# RegisterA.net
KiCad netlist of a schematic drawn in Altium Designer
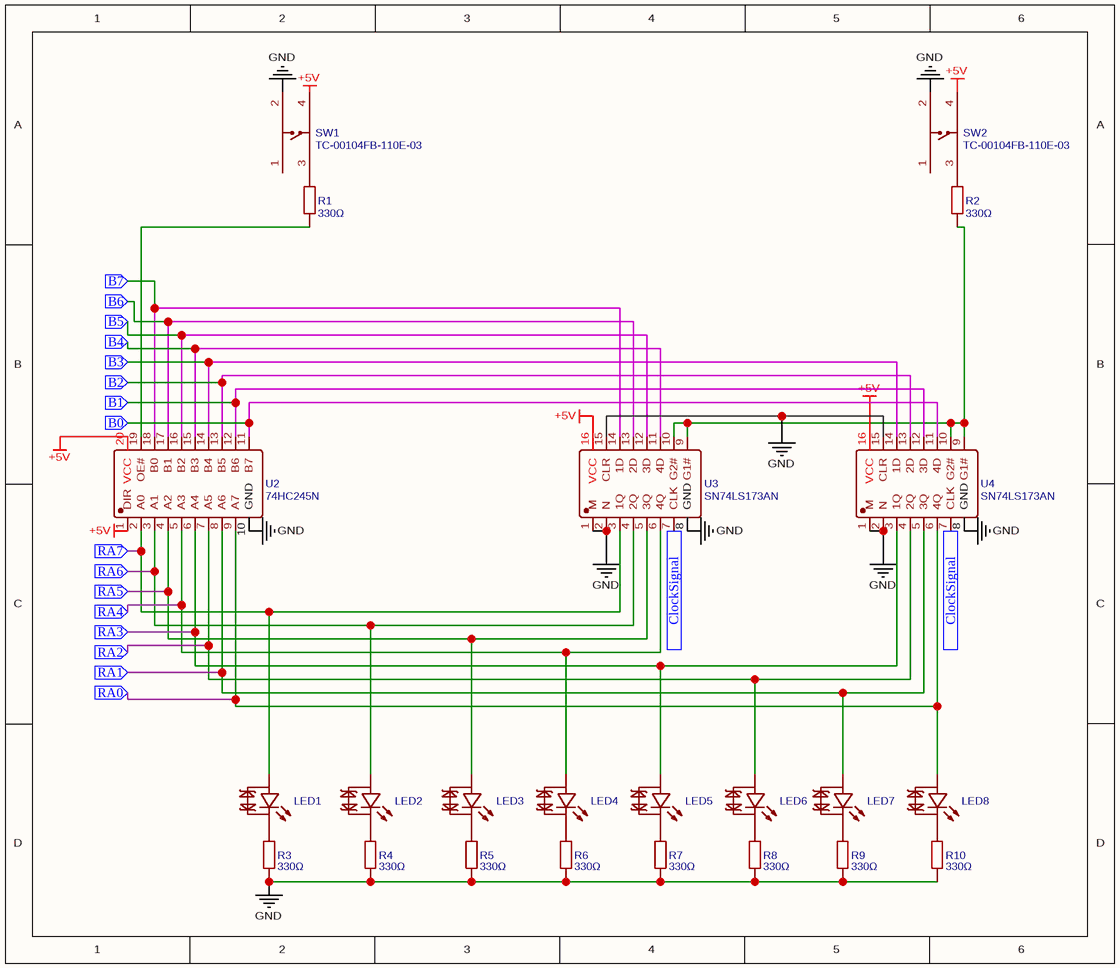
[diagram p0: RegisterA.schdoc]

(export (version "E")
  (design (tool "Eeschema 10.0.6"))
  (components
    (comp (ref "LED1")
      (value "204-15UTC/S400-X9-L")
      (fields (field (name "MANUFACTURER") "EVERLIGHT(亿光)") (field (name "CONTRIBUTOR") "LCSC"))
      (libsource (lib "altium-import") (part "root_3_204-15UTC/S400-X9-L_"))
    )
    (comp (ref "LED2")
      (value "204-15UTC/S400-X9-L")
      (fields (field (name "MANUFACTURER") "EVERLIGHT(亿光)") (field (name "CONTRIBUTOR") "LCSC"))
      (libsource (lib "altium-import") (part "root_3_204-15UTC/S400-X9-L_"))
    )
    (comp (ref "LED3")
      (value "204-15UTC/S400-X9-L")
      (fields (field (name "MANUFACTURER") "EVERLIGHT(亿光)") (field (name "CONTRIBUTOR") "LCSC"))
      (libsource (lib "altium-import") (part "root_3_204-15UTC/S400-X9-L_"))
    )
    (comp (ref "LED4")
      (value "204-15UTC/S400-X9-L")
      (fields (field (name "MANUFACTURER") "EVERLIGHT(亿光)") (field (name "CONTRIBUTOR") "LCSC"))
      (libsource (lib "altium-import") (part "root_3_204-15UTC/S400-X9-L_"))
    )
    (comp (ref "LED5")
      (value "204-15UTC/S400-X9-L")
      (fields (field (name "MANUFACTURER") "EVERLIGHT(亿光)") (field (name "CONTRIBUTOR") "LCSC"))
      (libsource (lib "altium-import") (part "root_3_204-15UTC/S400-X9-L_"))
    )
    (comp (ref "LED6")
      (value "204-15UTC/S400-X9-L")
      (fields (field (name "MANUFACTURER") "EVERLIGHT(亿光)") (field (name "CONTRIBUTOR") "LCSC"))
      (libsource (lib "altium-import") (part "root_3_204-15UTC/S400-X9-L_"))
    )
    (comp (ref "LED7")
      (value "204-15UTC/S400-X9-L")
      (fields (field (name "MANUFACTURER") "EVERLIGHT(亿光)") (field (name "CONTRIBUTOR") "LCSC"))
      (libsource (lib "altium-import") (part "root_3_204-15UTC/S400-X9-L_"))
    )
    (comp (ref "LED8")
      (value "204-15UTC/S400-X9-L")
      (fields (field (name "MANUFACTURER") "EVERLIGHT(亿光)") (field (name "CONTRIBUTOR") "LCSC"))
      (libsource (lib "altium-import") (part "root_3_204-15UTC/S400-X9-L_"))
    )
    (comp (ref "R1")
      (value "330Ω")
      (fields
        (field (name "MANUFACTURER") "CCO(千志电子)")
        (field (name "MANUFACTURER PART") "MF1/2W-0.1Ω±1% T")
        (field (name "CONTRIBUTOR") "LCSC")
      )
      (libsource (lib "altium-import") (part "root_1_330Ω_"))
    )
    (comp (ref "R2")
      (value "330Ω")
      (fields
        (field (name "MANUFACTURER") "CCO(千志电子)")
        (field (name "MANUFACTURER PART") "MF1/2W-0.1Ω±1% T")
        (field (name "CONTRIBUTOR") "LCSC")
      )
      (libsource (lib "altium-import") (part "root_1_330Ω_"))
    )
    (comp (ref "R3")
      (value "330Ω")
      (fields
        (field (name "MANUFACTURER") "CCO(千志电子)")
        (field (name "MANUFACTURER PART") "MF1/2W-0.1Ω±1% T")
        (field (name "CONTRIBUTOR") "LCSC")
      )
      (libsource (lib "altium-import") (part "root_3_330Ω_"))
    )
    (comp (ref "R4")
      (value "330Ω")
      (fields
        (field (name "MANUFACTURER") "CCO(千志电子)")
        (field (name "MANUFACTURER PART") "MF1/2W-0.1Ω±1% T")
        (field (name "CONTRIBUTOR") "LCSC")
      )
      (libsource (lib "altium-import") (part "root_3_330Ω_"))
    )
    (comp (ref "R5")
      (value "330Ω")
      (fields
        (field (name "MANUFACTURER") "CCO(千志电子)")
        (field (name "MANUFACTURER PART") "MF1/2W-0.1Ω±1% T")
        (field (name "CONTRIBUTOR") "LCSC")
      )
      (libsource (lib "altium-import") (part "root_3_330Ω_"))
    )
    (comp (ref "R6")
      (value "330Ω")
      (fields
        (field (name "MANUFACTURER") "CCO(千志电子)")
        (field (name "MANUFACTURER PART") "MF1/2W-0.1Ω±1% T")
        (field (name "CONTRIBUTOR") "LCSC")
      )
      (libsource (lib "altium-import") (part "root_3_330Ω_"))
    )
    (comp (ref "R7")
      (value "330Ω")
      (fields
        (field (name "MANUFACTURER") "CCO(千志电子)")
        (field (name "MANUFACTURER PART") "MF1/2W-0.1Ω±1% T")
        (field (name "CONTRIBUTOR") "LCSC")
      )
      (libsource (lib "altium-import") (part "root_3_330Ω_"))
    )
    (comp (ref "R8")
      (value "330Ω")
      (fields
        (field (name "MANUFACTURER") "CCO(千志电子)")
        (field (name "MANUFACTURER PART") "MF1/2W-0.1Ω±1% T")
        (field (name "CONTRIBUTOR") "LCSC")
      )
      (libsource (lib "altium-import") (part "root_3_330Ω_"))
    )
    (comp (ref "R9")
      (value "330Ω")
      (fields
        (field (name "MANUFACTURER") "CCO(千志电子)")
        (field (name "MANUFACTURER PART") "MF1/2W-0.1Ω±1% T")
        (field (name "CONTRIBUTOR") "LCSC")
      )
      (libsource (lib "altium-import") (part "root_3_330Ω_"))
    )
    (comp (ref "R10")
      (value "330Ω")
      (fields
        (field (name "MANUFACTURER") "CCO(千志电子)")
        (field (name "MANUFACTURER PART") "MF1/2W-0.1Ω±1% T")
        (field (name "CONTRIBUTOR") "LCSC")
      )
      (libsource (lib "altium-import") (part "root_3_330Ω_"))
    )
    (comp (ref "SW1")
      (value "TC-00104FB-110E-03")
      (fields (field (name "MANUFACTURER") "HOOYA(皓宇电子)") (field (name "CONTRIBUTOR") "lcsc"))
      (libsource (lib "altium-import") (part "root_1_TC-00104FB-110E-03_"))
    )
    (comp (ref "SW2")
      (value "TC-00104FB-110E-03")
      (fields (field (name "MANUFACTURER") "HOOYA(皓宇电子)") (field (name "CONTRIBUTOR") "lcsc"))
      (libsource (lib "altium-import") (part "root_1_TC-00104FB-110E-03_"))
    )
    (comp (ref "U2")
      (value "74HC245N")
      (fields (field (name "MANUFACTURER") "HGSEMI(华冠)") (field (name "CONTRIBUTOR") "LCSC"))
      (libsource (lib "altium-import") (part "root_1_74HC245N_"))
    )
    (comp (ref "U3")
      (value "SN74LS173AN")
      (fields (field (name "MANUFACTURER") "TI(德州仪器)") (field (name "CONTRIBUTOR") "LCSC"))
      (libsource (lib "altium-import") (part "root_1_SN74LS173AN_"))
    )
    (comp (ref "U4")
      (value "SN74LS173AN")
      (fields (field (name "MANUFACTURER") "TI(德州仪器)") (field (name "CONTRIBUTOR") "LCSC"))
      (libsource (lib "altium-import") (part "root_1_SN74LS173AN_"))
    )
  )
  (nets
    (net (code "1") (name "+5V") (class "Default")
      (node (ref "SW2") (pin "4") (pinfunction "4_4") (pintype "passive"))
      (node (ref "U2") (pin "1") (pinfunction "DIR_1") (pintype "passive"))
      (node (ref "U2") (pin "20") (pinfunction "VCC_20") (pintype "passive"))
      (node (ref "U3") (pin "16") (pinfunction "VCC_16") (pintype "passive"))
      (node (ref "U4") (pin "16") (pinfunction "VCC_16") (pintype "passive"))
    )
    (net (code "2") (name "/B0") (class "Default")
      (node (ref "U2") (pin "11") (pinfunction "B7_11") (pintype "passive"))
      (node (ref "U4") (pin "11") (pinfunction "4D_11") (pintype "passive"))
    )
    (net (code "3") (name "/B1") (class "Default")
      (node (ref "U2") (pin "12") (pinfunction "B6_12") (pintype "passive"))
      (node (ref "U4") (pin "12") (pinfunction "3D_12") (pintype "passive"))
    )
    (net (code "4") (name "/B2") (class "Default")
      (node (ref "U2") (pin "13") (pinfunction "B5_13") (pintype "passive"))
      (node (ref "U4") (pin "13") (pinfunction "2D_13") (pintype "passive"))
    )
    (net (code "5") (name "/B3") (class "Default")
      (node (ref "U2") (pin "14") (pinfunction "B4_14") (pintype "passive"))
      (node (ref "U4") (pin "14") (pinfunction "1D_14") (pintype "passive"))
    )
    (net (code "6") (name "/B4") (class "Default")
      (node (ref "U2") (pin "15") (pinfunction "B3_15") (pintype "passive"))
      (node (ref "U3") (pin "11") (pinfunction "4D_11") (pintype "passive"))
    )
    (net (code "7") (name "/B5") (class "Default")
      (node (ref "U2") (pin "16") (pinfunction "B2_16") (pintype "passive"))
      (node (ref "U3") (pin "12") (pinfunction "3D_12") (pintype "passive"))
    )
    (net (code "8") (name "/B6") (class "Default")
      (node (ref "U2") (pin "17") (pinfunction "B1_17") (pintype "passive"))
      (node (ref "U3") (pin "13") (pinfunction "2D_13") (pintype "passive"))
    )
    (net (code "9") (name "/B7") (class "Default")
      (node (ref "U2") (pin "18") (pinfunction "B0_18") (pintype "passive"))
      (node (ref "U3") (pin "14") (pinfunction "1D_14") (pintype "passive"))
    )
    (net (code "10") (name "/ClockSignal") (class "Default")
      (node (ref "U3") (pin "7") (pinfunction "CLK_7") (pintype "passive"))
      (node (ref "U4") (pin "7") (pinfunction "CLK_7") (pintype "passive"))
    )
    (net (code "11") (name "/RA0") (class "Default")
      (node (ref "LED8") (pin "1") (pinfunction "A_1") (pintype "passive"))
      (node (ref "U2") (pin "9") (pinfunction "A7_9") (pintype "passive"))
      (node (ref "U4") (pin "6") (pinfunction "4Q_6") (pintype "passive"))
    )
    (net (code "12") (name "/RA1") (class "Default")
      (node (ref "LED7") (pin "1") (pinfunction "A_1") (pintype "passive"))
      (node (ref "U2") (pin "8") (pinfunction "A6_8") (pintype "passive"))
      (node (ref "U4") (pin "5") (pinfunction "3Q_5") (pintype "passive"))
    )
    (net (code "13") (name "/RA2") (class "Default")
      (node (ref "LED6") (pin "1") (pinfunction "A_1") (pintype "passive"))
      (node (ref "U2") (pin "7") (pinfunction "A5_7") (pintype "passive"))
      (node (ref "U4") (pin "4") (pinfunction "2Q_4") (pintype "passive"))
    )
    (net (code "14") (name "/RA3") (class "Default")
      (node (ref "LED5") (pin "1") (pinfunction "A_1") (pintype "passive"))
      (node (ref "U2") (pin "6") (pinfunction "A4_6") (pintype "passive"))
      (node (ref "U4") (pin "3") (pinfunction "1Q_3") (pintype "passive"))
    )
    (net (code "15") (name "/RA4") (class "Default")
      (node (ref "LED4") (pin "1") (pinfunction "A_1") (pintype "passive"))
      (node (ref "U2") (pin "5") (pinfunction "A3_5") (pintype "passive"))
      (node (ref "U3") (pin "6") (pinfunction "4Q_6") (pintype "passive"))
    )
    (net (code "16") (name "/RA5") (class "Default")
      (node (ref "LED3") (pin "1") (pinfunction "A_1") (pintype "passive"))
      (node (ref "U2") (pin "4") (pinfunction "A2_4") (pintype "passive"))
      (node (ref "U3") (pin "5") (pinfunction "3Q_5") (pintype "passive"))
    )
    (net (code "17") (name "/RA6") (class "Default")
      (node (ref "LED2") (pin "1") (pinfunction "A_1") (pintype "passive"))
      (node (ref "U2") (pin "3") (pinfunction "A1_3") (pintype "passive"))
      (node (ref "U3") (pin "4") (pinfunction "2Q_4") (pintype "passive"))
    )
    (net (code "18") (name "/RA7") (class "Default")
      (node (ref "LED1") (pin "1") (pinfunction "A_1") (pintype "passive"))
      (node (ref "U2") (pin "2") (pinfunction "A0_2") (pintype "passive"))
      (node (ref "U3") (pin "3") (pinfunction "1Q_3") (pintype "passive"))
    )
    (net (code "19") (name "GND") (class "Default")
      (node (ref "R10") (pin "2") (pinfunction "2_2") (pintype "passive"))
      (node (ref "R3") (pin "2") (pinfunction "2_2") (pintype "passive"))
      (node (ref "R4") (pin "2") (pinfunction "2_2") (pintype "passive"))
      (node (ref "R5") (pin "2") (pinfunction "2_2") (pintype "passive"))
      (node (ref "R6") (pin "2") (pinfunction "2_2") (pintype "passive"))
      (node (ref "R7") (pin "2") (pinfunction "2_2") (pintype "passive"))
      (node (ref "R8") (pin "2") (pinfunction "2_2") (pintype "passive"))
      (node (ref "R9") (pin "2") (pinfunction "2_2") (pintype "passive"))
      (node (ref "SW1") (pin "2") (pinfunction "2_2") (pintype "passive"))
      (node (ref "SW2") (pin "2") (pinfunction "2_2") (pintype "passive"))
      (node (ref "U2") (pin "10") (pinfunction "GND_10") (pintype "passive"))
      (node (ref "U3") (pin "1") (pinfunction "M_1") (pintype "passive"))
      (node (ref "U3") (pin "15") (pinfunction "CLR_15") (pintype "passive"))
      (node (ref "U3") (pin "2") (pinfunction "N_2") (pintype "passive"))
      (node (ref "U3") (pin "8") (pinfunction "GND_8") (pintype "passive"))
      (node (ref "U4") (pin "1") (pinfunction "M_1") (pintype "passive"))
      (node (ref "U4") (pin "15") (pinfunction "CLR_15") (pintype "passive"))
      (node (ref "U4") (pin "2") (pinfunction "N_2") (pintype "passive"))
      (node (ref "U4") (pin "8") (pinfunction "GND_8") (pintype "passive"))
    )
    (net (code "20") (name "Net-(LED1-C)") (class "Default")
      (node (ref "LED1") (pin "2") (pinfunction "C_2") (pintype "passive"))
      (node (ref "R3") (pin "1") (pinfunction "1_1") (pintype "passive"))
    )
    (net (code "21") (name "Net-(LED2-C)") (class "Default")
      (node (ref "LED2") (pin "2") (pinfunction "C_2") (pintype "passive"))
      (node (ref "R4") (pin "1") (pinfunction "1_1") (pintype "passive"))
    )
    (net (code "22") (name "Net-(LED3-C)") (class "Default")
      (node (ref "LED3") (pin "2") (pinfunction "C_2") (pintype "passive"))
      (node (ref "R5") (pin "1") (pinfunction "1_1") (pintype "passive"))
    )
    (net (code "23") (name "Net-(LED4-C)") (class "Default")
      (node (ref "LED4") (pin "2") (pinfunction "C_2") (pintype "passive"))
      (node (ref "R6") (pin "1") (pinfunction "1_1") (pintype "passive"))
    )
    (net (code "24") (name "Net-(LED5-C)") (class "Default")
      (node (ref "LED5") (pin "2") (pinfunction "C_2") (pintype "passive"))
      (node (ref "R7") (pin "1") (pinfunction "1_1") (pintype "passive"))
    )
    (net (code "25") (name "Net-(LED6-C)") (class "Default")
      (node (ref "LED6") (pin "2") (pinfunction "C_2") (pintype "passive"))
      (node (ref "R8") (pin "1") (pinfunction "1_1") (pintype "passive"))
    )
    (net (code "26") (name "Net-(LED7-C)") (class "Default")
      (node (ref "LED7") (pin "2") (pinfunction "C_2") (pintype "passive"))
      (node (ref "R9") (pin "1") (pinfunction "1_1") (pintype "passive"))
    )
    (net (code "27") (name "Net-(LED8-C)") (class "Default")
      (node (ref "LED8") (pin "2") (pinfunction "C_2") (pintype "passive"))
      (node (ref "R10") (pin "1") (pinfunction "1_1") (pintype "passive"))
    )
    (net (code "28") (name "Net-(R1-Pad2)") (class "Default")
      (node (ref "R1") (pin "2") (pinfunction "2_2") (pintype "passive"))
      (node (ref "SW1") (pin "3") (pinfunction "3_3") (pintype "passive"))
    )
    (net (code "29") (name "Net-(R2-Pad2)") (class "Default")
      (node (ref "R2") (pin "2") (pinfunction "2_2") (pintype "passive"))
      (node (ref "SW2") (pin "3") (pinfunction "3_3") (pintype "passive"))
    )
    (net (code "30") (name "Net-(U2-OE#)") (class "Default")
      (node (ref "R1") (pin "1") (pinfunction "1_1") (pintype "passive"))
      (node (ref "U2") (pin "19") (pinfunction "OE#_19") (pintype "passive"))
    )
    (net (code "31") (name "Net-(U3-G1#)") (class "Default")
      (node (ref "R2") (pin "1") (pinfunction "1_1") (pintype "passive"))
      (node (ref "U3") (pin "10") (pinfunction "G2#_10") (pintype "passive"))
      (node (ref "U3") (pin "9") (pinfunction "G1#_9") (pintype "passive"))
      (node (ref "U4") (pin "10") (pinfunction "G2#_10") (pintype "passive"))
      (node (ref "U4") (pin "9") (pinfunction "G1#_9") (pintype "passive"))
    )
    (net (code "32") (name "unconnected-(SW1-Pad1)") (class "Default")
      (node (ref "SW1") (pin "1") (pinfunction "1_1") (pintype "passive"))
    )
    (net (code "33") (name "unconnected-(SW1-Pad4)") (class "Default")
      (node (ref "SW1") (pin "4") (pinfunction "4_4") (pintype "passive"))
    )
    (net (code "34") (name "unconnected-(SW2-Pad1)") (class "Default")
      (node (ref "SW2") (pin "1") (pinfunction "1_1") (pintype "passive"))
    )
  )
)
